# DC075B_DTGC_CPLD.net
KiCad netlist of a schematic drawn in Altium Designer
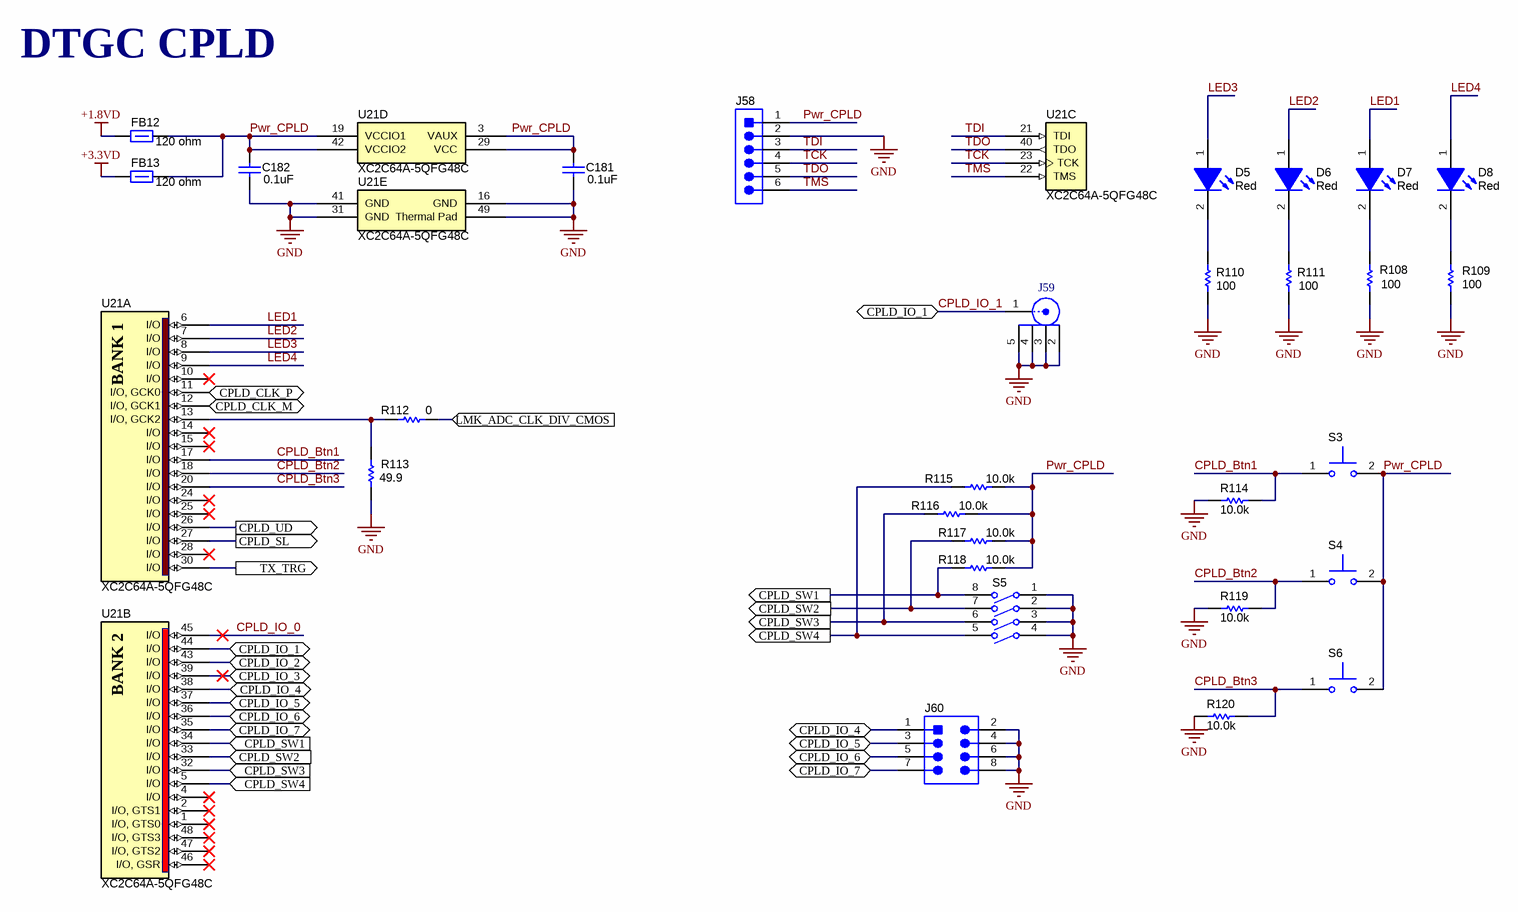
[diagram p0: DC075B_DTGC_CPLD.SchDoc]

(export (version "E")
  (design (tool "Eeschema 10.0.6"))
  (components
    (comp (ref "C181")
      (value "0.1uF")
      (footprint "0603")
      (description "CAP, CERM, 0.1 µF, 25 V,+/- 10%, X5R, 0603")
      (fields
        (field (name "PARTNUMBER") "CL10A104KA8NNNC")
        (field (name "MANUFACTURER") "Samsung Electro-Mechanics")
      )
      (libsource (lib "Altium Vault - TI") (part "Capacitor"))
    )
    (comp (ref "C182")
      (value "0.1uF")
      (footprint "0603")
      (description "CAP, CERM, 0.1 µF, 25 V,+/- 10%, X5R, 0603")
      (fields
        (field (name "PARTNUMBER") "CL10A104KA8NNNC")
        (field (name "MANUFACTURER") "Samsung Electro-Mechanics")
      )
      (libsource (lib "Altium Vault - TI") (part "Capacitor"))
    )
    (comp (ref "D5")
      (value "Red")
      (footprint "LED_LTST-C190_Red")
      (description "LED, Red, SMD")
      (fields (field (name "MANUFACTURER") "Lite-On") (field (name "PARTNUMBER") "LTST-C190CKT"))
      (libsource (lib "Altium Vault - TI") (part "CMP-0002842-2"))
    )
    (comp (ref "D6")
      (value "Red")
      (footprint "LED_LTST-C190_Red")
      (description "LED, Red, SMD")
      (fields (field (name "MANUFACTURER") "Lite-On") (field (name "PARTNUMBER") "LTST-C190CKT"))
      (libsource (lib "Altium Vault - TI") (part "CMP-0002842-2"))
    )
    (comp (ref "D7")
      (value "Red")
      (footprint "LED_LTST-C190_Red")
      (description "LED, Red, SMD")
      (fields (field (name "MANUFACTURER") "Lite-On") (field (name "PARTNUMBER") "LTST-C190CKT"))
      (libsource (lib "Altium Vault - TI") (part "CMP-0002842-2"))
    )
    (comp (ref "D8")
      (value "Red")
      (footprint "LED_LTST-C190_Red")
      (description "LED, Red, SMD")
      (fields (field (name "MANUFACTURER") "Lite-On") (field (name "PARTNUMBER") "LTST-C190CKT"))
      (libsource (lib "Altium Vault - TI") (part "CMP-0002842-2"))
    )
    (comp (ref "FB12")
      (value "120 ohm")
      (footprint "0805")
      (description "Ferrite Bead, 120 ohm @ 100 MHz, 0.8 A, 0805")
      (fields
        (field (name "MANUFACTURER") "MuRata")
        (field (name "PARTNUMBER") "BLM21AG121SN1D")
        (field (name "PUBLISHER") "Texas Instruments")
      )
      (libsource (lib "Altium Vault - TI") (part "Ferrite_Bead"))
    )
    (comp (ref "FB13")
      (value "120 ohm")
      (footprint "0805")
      (description "Ferrite Bead, 120 ohm @ 100 MHz, 0.8 A, 0805")
      (fields
        (field (name "MANUFACTURER") "MuRata")
        (field (name "PARTNUMBER") "BLM21AG121SN1D")
        (field (name "PUBLISHER") "Texas Instruments")
      )
      (libsource (lib "Altium Vault - TI") (part "Ferrite_Bead"))
    )
    (comp (ref "J58")
      (value "Header_6x1")
      (footprint "TSW-106-07-G-S")
      (description "Header, 100mil, 6x1, Gold, TH")
      (fields (field (name "PARTNUMBER") "TSW-106-07-G-S") (field (name "MANUFACTURER") "Samtec"))
      (libsource (lib "Altium Vault - TI") (part "Header_6x1"))
    )
    (comp (ref "J59")
      (value "5-1814832-1")
      (footprint "TE_5-1814832-1")
      (description "SMA Straight PCB Socket Die Cast, 50 Ohm, TH")
      (fields (field (name "MANUFACTURER") "TE Connectivity") (field (name "PUBLISHER") "Texas Instruments"))
      (libsource (lib "Altium Vault - TI") (part "SMA_Contact1_GND2345"))
    )
    (comp (ref "J60")
      (value "Header_4x2")
      (footprint "TSW-104-07-G-D")
      (description "Header, 100mil, 4x2, Gold, TH")
      (fields (field (name "PARTNUMBER") "TSW-104-07-G-D") (field (name "MANUFACTURER") "Samtec"))
      (libsource (lib "Altium Vault - TI") (part "Header_4x2"))
    )
    (comp (ref "R108")
      (value "Resistor")
      (footprint "0402")
      (description "RES, 100, 1%, 0.1 W, 0402")
      (fields
        (field (name "MANUFACTURER") "Panasonic")
        (field (name "PARTNUMBER") "ERJ-2RKF1000X")
        (field (name "VALUEDISPLAYED") "100")
        (field (name "PUBLISHER") "Texas Instruments")
      )
      (libsource (lib "Altium Vault - TI") (part "Resistor"))
    )
    (comp (ref "R109")
      (value "Resistor")
      (footprint "0402")
      (description "RES, 100, 1%, 0.1 W, 0402")
      (fields
        (field (name "MANUFACTURER") "Panasonic")
        (field (name "PARTNUMBER") "ERJ-2RKF1000X")
        (field (name "VALUEDISPLAYED") "100")
        (field (name "PUBLISHER") "Texas Instruments")
      )
      (libsource (lib "Altium Vault - TI") (part "Resistor"))
    )
    (comp (ref "R110")
      (value "Resistor")
      (footprint "0402")
      (description "RES, 100, 1%, 0.1 W, 0402")
      (fields
        (field (name "MANUFACTURER") "Panasonic")
        (field (name "PARTNUMBER") "ERJ-2RKF1000X")
        (field (name "VALUEDISPLAYED") "100")
        (field (name "PUBLISHER") "Texas Instruments")
      )
      (libsource (lib "Altium Vault - TI") (part "Resistor"))
    )
    (comp (ref "R111")
      (value "Resistor")
      (footprint "0402")
      (description "RES, 100, 1%, 0.1 W, 0402")
      (fields
        (field (name "MANUFACTURER") "Panasonic")
        (field (name "PARTNUMBER") "ERJ-2RKF1000X")
        (field (name "VALUEDISPLAYED") "100")
        (field (name "PUBLISHER") "Texas Instruments")
      )
      (libsource (lib "Altium Vault - TI") (part "Resistor"))
    )
    (comp (ref "R112")
      (value "0")
      (footprint "0402")
      (description "RES, 0, 5%, 0.063 W, AEC-Q200 Grade 0, 0402")
      (fields (field (name "MANUFACTURER") "Vishay-Dale") (field (name "PARTNUMBER") "CRCW04020000Z0ED"))
      (libsource (lib "Altium Vault - TI") (part "Resistor"))
    )
    (comp (ref "R113")
      (value "49.9")
      (footprint "0402")
      (description "RES, 49.9, 1%, 0.063 W, AEC-Q200 Grade 0, 0402")
      (fields (field (name "MANUFACTURER") "Vishay-Dale") (field (name "PARTNUMBER") "CRCW040249R9FKED"))
      (libsource (lib "Altium Vault - TI") (part "Resistor"))
    )
    (comp (ref "R114")
      (value "10.0k")
      (footprint "0603")
      (description "RES, 10.0 k, 1%, 0.1 W, 0603")
      (fields
        (field (name "MANUFACTURER") "Panasonic")
        (field (name "PARTNUMBER") "ERJ-3EKF1002V")
        (field (name "PUBLISHER") "Texas Instruments")
      )
      (libsource (lib "Altium Vault - TI") (part "Resistor"))
    )
    (comp (ref "R115")
      (value "10.0k")
      (footprint "0603")
      (description "RES, 10.0 k, 1%, 0.1 W, 0603")
      (fields
        (field (name "MANUFACTURER") "Panasonic")
        (field (name "PARTNUMBER") "ERJ-3EKF1002V")
        (field (name "PUBLISHER") "Texas Instruments")
      )
      (libsource (lib "Altium Vault - TI") (part "Resistor"))
    )
    (comp (ref "R116")
      (value "10.0k")
      (footprint "0603")
      (description "RES, 10.0 k, 1%, 0.1 W, 0603")
      (fields
        (field (name "MANUFACTURER") "Panasonic")
        (field (name "PARTNUMBER") "ERJ-3EKF1002V")
        (field (name "PUBLISHER") "Texas Instruments")
      )
      (libsource (lib "Altium Vault - TI") (part "Resistor"))
    )
    (comp (ref "R117")
      (value "10.0k")
      (footprint "0603")
      (description "RES, 10.0 k, 1%, 0.1 W, 0603")
      (fields
        (field (name "MANUFACTURER") "Panasonic")
        (field (name "PARTNUMBER") "ERJ-3EKF1002V")
        (field (name "PUBLISHER") "Texas Instruments")
      )
      (libsource (lib "Altium Vault - TI") (part "Resistor"))
    )
    (comp (ref "R118")
      (value "10.0k")
      (footprint "0603")
      (description "RES, 10.0 k, 1%, 0.1 W, 0603")
      (fields
        (field (name "MANUFACTURER") "Panasonic")
        (field (name "PARTNUMBER") "ERJ-3EKF1002V")
        (field (name "PUBLISHER") "Texas Instruments")
      )
      (libsource (lib "Altium Vault - TI") (part "Resistor"))
    )
    (comp (ref "R119")
      (value "10.0k")
      (footprint "0603")
      (description "RES, 10.0 k, 1%, 0.1 W, 0603")
      (fields
        (field (name "MANUFACTURER") "Panasonic")
        (field (name "PARTNUMBER") "ERJ-3EKF1002V")
        (field (name "PUBLISHER") "Texas Instruments")
      )
      (libsource (lib "Altium Vault - TI") (part "Resistor"))
    )
    (comp (ref "R120")
      (value "10.0k")
      (footprint "0603")
      (description "RES, 10.0 k, 1%, 0.1 W, 0603")
      (fields
        (field (name "MANUFACTURER") "Panasonic")
        (field (name "PARTNUMBER") "ERJ-3EKF1002V")
        (field (name "PUBLISHER") "Texas Instruments")
      )
      (libsource (lib "Altium Vault - TI") (part "Resistor"))
    )
    (comp (ref "S3")
      (value "SKRKAEE020")
      (footprint "SW_SKRKAE")
      (description "Switch, SPST-NO, 0.05 A, 12 VDC, SMT")
      (fields (field (name "MANUFACTURER") "Alps") (field (name "PUBLISHER") "Texas Instruments"))
      (libsource (lib "Altium Vault - TI") (part "Switch_PushButton"))
    )
    (comp (ref "S4")
      (value "SKRKAEE020")
      (footprint "SW_SKRKAE")
      (description "Switch, SPST-NO, 0.05 A, 12 VDC, SMT")
      (fields (field (name "MANUFACTURER") "Alps") (field (name "PUBLISHER") "Texas Instruments"))
      (libsource (lib "Altium Vault - TI") (part "Switch_PushButton"))
    )
    (comp (ref "S5")
      (value "SW_4SPST")
      (footprint "SW_1571983-5")
      (description "Switch, SPST, 4 Pos, Top Actuated, SMD")
      (fields
        (field (name "PARTNUMBER") "1571983-5")
        (field (name "MANUFACTURER") "TE Connectivity")
        (field (name "PUBLISHER") "Texas Instruments")
      )
      (libsource (lib "Altium Vault - TI") (part "SW_4SPST"))
    )
    (comp (ref "S6")
      (value "SKRKAEE020")
      (footprint "SW_SKRKAE")
      (description "Switch, SPST-NO, 0.05 A, 12 VDC, SMT")
      (fields (field (name "MANUFACTURER") "Alps") (field (name "PUBLISHER") "Texas Instruments"))
      (libsource (lib "Altium Vault - TI") (part "Switch_PushButton"))
    )
    (comp (ref "U21")
      (value "XC2C64A-5QFG48C")
      (footprint "QFG48_N")
      (description "XC2C64A CoolRunner-II CPLD, QFG48")
      (fields (field (name "MANUFACTURER") "Xilinx") (field (name "PUBLISHER") "Texas Instruments"))
      (libsource (lib "Altium Vault - TI") (part "XC2C64A-5QFG48C"))
    )
  )
  (nets
    (net (code "1") (name "+1.8VD") (class "Default")
      (node (ref "FB12") (pin "2") (pinfunction "2_2") (pintype "passive"))
    )
    (net (code "2") (name "+3.3VD") (class "Default")
      (node (ref "FB13") (pin "2") (pinfunction "2_2") (pintype "passive"))
    )
    (net (code "3") (name "/CPLD_Btn1") (class "Default")
      (node (ref "R114") (pin "1") (pinfunction "1_1") (pintype "passive"))
      (node (ref "S3") (pin "1") (pinfunction "1_1") (pintype "passive"))
      (node (ref "U21") (pin "17") (pinfunction "I/O_17") (pintype "bidirectional"))
    )
    (net (code "4") (name "/CPLD_Btn2") (class "Default")
      (node (ref "R119") (pin "1") (pinfunction "1_1") (pintype "passive"))
      (node (ref "S4") (pin "1") (pinfunction "1_1") (pintype "passive"))
      (node (ref "U21") (pin "18") (pinfunction "I/O_18") (pintype "bidirectional"))
    )
    (net (code "5") (name "/CPLD_Btn3") (class "Default")
      (node (ref "R120") (pin "1") (pinfunction "1_1") (pintype "passive"))
      (node (ref "S6") (pin "1") (pinfunction "1_1") (pintype "passive"))
      (node (ref "U21") (pin "20") (pinfunction "I/O_20") (pintype "bidirectional"))
    )
    (net (code "6") (name "/CPLD_CLK_M") (class "Default")
      (node (ref "U21") (pin "12") (pinfunction "I/O,_GCK1_12") (pintype "bidirectional"))
    )
    (net (code "7") (name "/CPLD_CLK_P") (class "Default")
      (node (ref "U21") (pin "11") (pinfunction "I/O,_GCK0_11") (pintype "bidirectional"))
    )
    (net (code "8") (name "/CPLD_IO_0") (class "Default")
      (node (ref "U21") (pin "45") (pinfunction "I/O_45") (pintype "bidirectional"))
    )
    (net (code "9") (name "/CPLD_IO_1") (class "Default")
      (node (ref "J59") (pin "1") (pinfunction "1_1") (pintype "passive"))
      (node (ref "U21") (pin "44") (pinfunction "I/O_44") (pintype "bidirectional"))
    )
    (net (code "10") (name "/CPLD_IO_2") (class "Default")
      (node (ref "U21") (pin "43") (pinfunction "I/O_43") (pintype "bidirectional"))
    )
    (net (code "11") (name "/CPLD_IO_3") (class "Default")
      (node (ref "U21") (pin "39") (pinfunction "I/O_39") (pintype "bidirectional"))
    )
    (net (code "12") (name "/CPLD_IO_4") (class "Default")
      (node (ref "J60") (pin "1") (pinfunction "1_1") (pintype "passive"))
      (node (ref "U21") (pin "38") (pinfunction "I/O_38") (pintype "bidirectional"))
    )
    (net (code "13") (name "/CPLD_IO_5") (class "Default")
      (node (ref "J60") (pin "3") (pinfunction "3_3") (pintype "passive"))
      (node (ref "U21") (pin "37") (pinfunction "I/O_37") (pintype "bidirectional"))
    )
    (net (code "14") (name "/CPLD_IO_6") (class "Default")
      (node (ref "J60") (pin "5") (pinfunction "5_5") (pintype "passive"))
      (node (ref "U21") (pin "36") (pinfunction "I/O_36") (pintype "bidirectional"))
    )
    (net (code "15") (name "/CPLD_IO_7") (class "Default")
      (node (ref "J60") (pin "7") (pinfunction "7_7") (pintype "passive"))
      (node (ref "U21") (pin "35") (pinfunction "I/O_35") (pintype "bidirectional"))
    )
    (net (code "16") (name "/CPLD_SL") (class "Default")
      (node (ref "U21") (pin "27") (pinfunction "I/O_27") (pintype "bidirectional"))
    )
    (net (code "17") (name "/CPLD_SW1") (class "Default")
      (node (ref "R118") (pin "1") (pinfunction "1_1") (pintype "passive"))
      (node (ref "S5") (pin "8") (pinfunction "B1_8") (pintype "passive"))
      (node (ref "U21") (pin "34") (pinfunction "I/O_34") (pintype "bidirectional"))
    )
    (net (code "18") (name "/CPLD_SW2") (class "Default")
      (node (ref "R117") (pin "1") (pinfunction "1_1") (pintype "passive"))
      (node (ref "S5") (pin "7") (pinfunction "B2_7") (pintype "passive"))
      (node (ref "U21") (pin "33") (pinfunction "I/O_33") (pintype "bidirectional"))
    )
    (net (code "19") (name "/CPLD_SW3") (class "Default")
      (node (ref "R116") (pin "1") (pinfunction "1_1") (pintype "passive"))
      (node (ref "S5") (pin "6") (pinfunction "B3_6") (pintype "passive"))
      (node (ref "U21") (pin "32") (pinfunction "I/O_32") (pintype "bidirectional"))
    )
    (net (code "20") (name "/CPLD_SW4") (class "Default")
      (node (ref "R115") (pin "1") (pinfunction "1_1") (pintype "passive"))
      (node (ref "S5") (pin "5") (pinfunction "B4_5") (pintype "passive"))
      (node (ref "U21") (pin "5") (pinfunction "I/O_5") (pintype "bidirectional"))
    )
    (net (code "21") (name "/CPLD_UD") (class "Default")
      (node (ref "U21") (pin "26") (pinfunction "I/O_26") (pintype "bidirectional"))
    )
    (net (code "22") (name "/LED1") (class "Default")
      (node (ref "D7") (pin "1") (pinfunction "A_1") (pintype "passive"))
      (node (ref "U21") (pin "6") (pinfunction "I/O_6") (pintype "bidirectional"))
    )
    (net (code "23") (name "/LED2") (class "Default")
      (node (ref "D6") (pin "1") (pinfunction "A_1") (pintype "passive"))
      (node (ref "U21") (pin "7") (pinfunction "I/O_7") (pintype "bidirectional"))
    )
    (net (code "24") (name "/LED3") (class "Default")
      (node (ref "D5") (pin "1") (pinfunction "A_1") (pintype "passive"))
      (node (ref "U21") (pin "8") (pinfunction "I/O_8") (pintype "bidirectional"))
    )
    (net (code "25") (name "/LED4") (class "Default")
      (node (ref "D8") (pin "1") (pinfunction "A_1") (pintype "passive"))
      (node (ref "U21") (pin "9") (pinfunction "I/O_9") (pintype "bidirectional"))
    )
    (net (code "26") (name "/LMK_ADC_CLK_DIV_CMOS") (class "Default")
      (node (ref "R112") (pin "1") (pinfunction "1_1") (pintype "passive"))
    )
    (net (code "27") (name "/Pwr_CPLD") (class "Default")
      (node (ref "C181") (pin "1") (pinfunction "1_1") (pintype "passive"))
      (node (ref "C182") (pin "1") (pinfunction "1_1") (pintype "passive"))
      (node (ref "FB12") (pin "1") (pinfunction "1_1") (pintype "passive"))
      (node (ref "FB13") (pin "1") (pinfunction "1_1") (pintype "passive"))
      (node (ref "J58") (pin "1") (pinfunction "1_1") (pintype "passive"))
      (node (ref "R115") (pin "2") (pinfunction "2_2") (pintype "passive"))
      (node (ref "R116") (pin "2") (pinfunction "2_2") (pintype "passive"))
      (node (ref "R117") (pin "2") (pinfunction "2_2") (pintype "passive"))
      (node (ref "R118") (pin "2") (pinfunction "2_2") (pintype "passive"))
      (node (ref "S3") (pin "2") (pinfunction "2_2") (pintype "passive"))
      (node (ref "S4") (pin "2") (pinfunction "2_2") (pintype "passive"))
      (node (ref "S6") (pin "2") (pinfunction "2_2") (pintype "passive"))
      (node (ref "U21") (pin "19") (pinfunction "VCCIO1_19") (pintype "power_in"))
      (node (ref "U21") (pin "29") (pinfunction "VCC_29") (pintype "power_in"))
      (node (ref "U21") (pin "3") (pinfunction "VAUX_3") (pintype "power_in"))
      (node (ref "U21") (pin "42") (pinfunction "VCCIO2_42") (pintype "power_in"))
    )
    (net (code "28") (name "/TCK") (class "Default")
      (node (ref "J58") (pin "4") (pinfunction "4_4") (pintype "passive"))
      (node (ref "U21") (pin "23") (pinfunction "TCK_23") (pintype "input"))
    )
    (net (code "29") (name "/TDI") (class "Default")
      (node (ref "J58") (pin "3") (pinfunction "3_3") (pintype "passive"))
      (node (ref "U21") (pin "21") (pinfunction "TDI_21") (pintype "input"))
    )
    (net (code "30") (name "/TDO") (class "Default")
      (node (ref "J58") (pin "5") (pinfunction "5_5") (pintype "passive"))
      (node (ref "U21") (pin "40") (pinfunction "TDO_40") (pintype "output"))
    )
    (net (code "31") (name "/TMS") (class "Default")
      (node (ref "J58") (pin "6") (pinfunction "6_6") (pintype "passive"))
      (node (ref "U21") (pin "22") (pinfunction "TMS_22") (pintype "input"))
    )
    (net (code "32") (name "/TX_TRG") (class "Default")
      (node (ref "U21") (pin "30") (pinfunction "I/O_30") (pintype "bidirectional"))
    )
    (net (code "33") (name "GND") (class "Default")
      (node (ref "C181") (pin "2") (pinfunction "2_2") (pintype "passive"))
      (node (ref "C182") (pin "2") (pinfunction "2_2") (pintype "passive"))
      (node (ref "J58") (pin "2") (pinfunction "2_2") (pintype "passive"))
      (node (ref "J59") (pin "2") (pinfunction "2_2") (pintype "passive"))
      (node (ref "J59") (pin "3") (pinfunction "3_3") (pintype "passive"))
      (node (ref "J59") (pin "4") (pinfunction "4_4") (pintype "passive"))
      (node (ref "J59") (pin "5") (pinfunction "5_5") (pintype "passive"))
      (node (ref "J60") (pin "2") (pinfunction "2_2") (pintype "passive"))
      (node (ref "J60") (pin "4") (pinfunction "4_4") (pintype "passive"))
      (node (ref "J60") (pin "6") (pinfunction "6_6") (pintype "passive"))
      (node (ref "J60") (pin "8") (pinfunction "8_8") (pintype "passive"))
      (node (ref "R108") (pin "1") (pinfunction "1_1") (pintype "passive"))
      (node (ref "R109") (pin "1") (pinfunction "1_1") (pintype "passive"))
      (node (ref "R110") (pin "1") (pinfunction "1_1") (pintype "passive"))
      (node (ref "R111") (pin "1") (pinfunction "1_1") (pintype "passive"))
      (node (ref "R113") (pin "2") (pinfunction "2_2") (pintype "passive"))
      (node (ref "R114") (pin "2") (pinfunction "2_2") (pintype "passive"))
      (node (ref "R119") (pin "2") (pinfunction "2_2") (pintype "passive"))
      (node (ref "R120") (pin "2") (pinfunction "2_2") (pintype "passive"))
      (node (ref "S5") (pin "1") (pinfunction "A1_1") (pintype "passive"))
      (node (ref "S5") (pin "2") (pinfunction "A2_2") (pintype "passive"))
      (node (ref "S5") (pin "3") (pinfunction "A3_3") (pintype "passive"))
      (node (ref "S5") (pin "4") (pinfunction "A4_4") (pintype "passive"))
      (node (ref "U21") (pin "16") (pinfunction "GND_16") (pintype "power_in"))
      (node (ref "U21") (pin "31") (pinfunction "GND_31") (pintype "power_in"))
      (node (ref "U21") (pin "41") (pinfunction "GND_41") (pintype "power_in"))
      (node (ref "U21") (pin "49") (pinfunction "Thermal_Pad_49") (pintype "power_in"))
    )
    (net (code "34") (name "Net-(D5-K)") (class "Default")
      (node (ref "D5") (pin "2") (pinfunction "K_2") (pintype "passive"))
      (node (ref "R110") (pin "2") (pinfunction "2_2") (pintype "passive"))
    )
    (net (code "35") (name "Net-(D6-K)") (class "Default")
      (node (ref "D6") (pin "2") (pinfunction "K_2") (pintype "passive"))
      (node (ref "R111") (pin "2") (pinfunction "2_2") (pintype "passive"))
    )
    (net (code "36") (name "Net-(D7-K)") (class "Default")
      (node (ref "D7") (pin "2") (pinfunction "K_2") (pintype "passive"))
      (node (ref "R108") (pin "2") (pinfunction "2_2") (pintype "passive"))
    )
    (net (code "37") (name "Net-(D8-K)") (class "Default")
      (node (ref "D8") (pin "2") (pinfunction "K_2") (pintype "passive"))
      (node (ref "R109") (pin "2") (pinfunction "2_2") (pintype "passive"))
    )
    (net (code "38") (name "Net-(U21A-I{slash}O,_GCK2)") (class "Default")
      (node (ref "R112") (pin "2") (pinfunction "2_2") (pintype "passive"))
      (node (ref "R113") (pin "1") (pinfunction "1_1") (pintype "passive"))
      (node (ref "U21") (pin "13") (pinfunction "I/O,_GCK2_13") (pintype "bidirectional"))
    )
    (net (code "39") (name "unconnected-(U21A-I{slash}O-Pad10)") (class "Default")
      (node (ref "U21") (pin "10") (pinfunction "I/O_10") (pintype "bidirectional+no_connect"))
    )
    (net (code "40") (name "unconnected-(U21A-I{slash}O-Pad14)") (class "Default")
      (node (ref "U21") (pin "14") (pinfunction "I/O_14") (pintype "bidirectional+no_connect"))
    )
    (net (code "41") (name "unconnected-(U21A-I{slash}O-Pad15)") (class "Default")
      (node (ref "U21") (pin "15") (pinfunction "I/O_15") (pintype "bidirectional+no_connect"))
    )
    (net (code "42") (name "unconnected-(U21A-I{slash}O-Pad24)") (class "Default")
      (node (ref "U21") (pin "24") (pinfunction "I/O_24") (pintype "bidirectional+no_connect"))
    )
    (net (code "43") (name "unconnected-(U21A-I{slash}O-Pad25)") (class "Default")
      (node (ref "U21") (pin "25") (pinfunction "I/O_25") (pintype "bidirectional+no_connect"))
    )
    (net (code "44") (name "unconnected-(U21A-I{slash}O-Pad28)") (class "Default")
      (node (ref "U21") (pin "28") (pinfunction "I/O_28") (pintype "bidirectional+no_connect"))
    )
    (net (code "45") (name "unconnected-(U21B-I{slash}O,_GSR-Pad46)") (class "Default")
      (node (ref "U21") (pin "46") (pinfunction "I/O,_GSR_46") (pintype "bidirectional+no_connect"))
    )
    (net (code "46") (name "unconnected-(U21B-I{slash}O,_GTS0-Pad1)") (class "Default")
      (node (ref "U21") (pin "1") (pinfunction "I/O,_GTS0_1") (pintype "bidirectional+no_connect"))
    )
    (net (code "47") (name "unconnected-(U21B-I{slash}O,_GTS1-Pad2)") (class "Default")
      (node (ref "U21") (pin "2") (pinfunction "I/O,_GTS1_2") (pintype "bidirectional+no_connect"))
    )
    (net (code "48") (name "unconnected-(U21B-I{slash}O,_GTS2-Pad47)") (class "Default")
      (node (ref "U21") (pin "47") (pinfunction "I/O,_GTS2_47") (pintype "bidirectional+no_connect"))
    )
    (net (code "49") (name "unconnected-(U21B-I{slash}O,_GTS3-Pad48)") (class "Default")
      (node (ref "U21") (pin "48") (pinfunction "I/O,_GTS3_48") (pintype "bidirectional+no_connect"))
    )
    (net (code "50") (name "unconnected-(U21B-I{slash}O-Pad4)") (class "Default")
      (node (ref "U21") (pin "4") (pinfunction "I/O_4") (pintype "bidirectional+no_connect"))
    )
  )
)
